# 3V3_LDO.net
KiCad netlist of a schematic drawn in Altium Designer
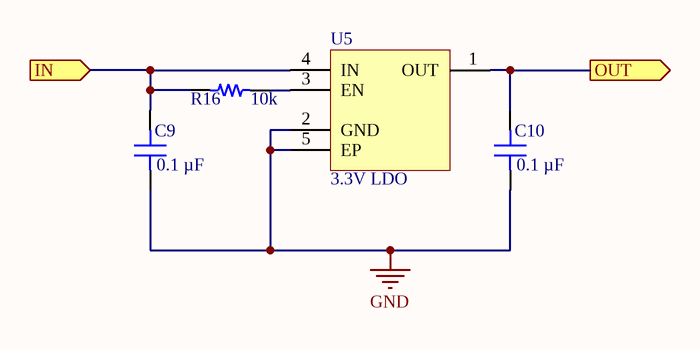
[diagram p0: 3V3_LDO.SchDoc]

(export (version "E")
  (design (tool "Eeschema 10.0.6"))
  (components
    (comp (ref "C9")
      (value "0.1 µF")
      (footprint "CAP 0402_1005")
      (description "CAP CER 0.1UF 16V X7R 0402")
      (fields (field (name "PART NUMBER") "C0402C104K4RACAUTO") (field (name "MANUFACTURER") "KEMET"))
      (libsource (lib "Celestial Altium Library - altium_library") (part "Capacitor"))
    )
    (comp (ref "C10")
      (value "0.1 µF")
      (footprint "CAP 0402_1005")
      (description "CAP CER 0.1UF 16V X7R 0402")
      (fields (field (name "PART NUMBER") "C0402C104K4RACAUTO") (field (name "MANUFACTURER") "KEMET"))
      (libsource (lib "Celestial Altium Library - altium_library") (part "Capacitor"))
    )
    (comp (ref "R16")
      (value "10k")
      (footprint "RES 0402_1005")
      (description "RES 5.62K OHM 0.1% 1/10W 0402")
      (fields
        (field (name "PART NUMBER") "RP73PF1E5K62BTD")
        (field (name "MANUFACTURER") "TE Connectivity Passive Product")
      )
      (libsource (lib "Celestial Altium Library - altium_library") (part "Resistor"))
    )
    (comp (ref "U5") (value "3.3V LDO") (footprint "XDFN-4") (libsource (lib "IC") (part "TLV74033PDQNR")))
  )
  (nets
    (net (code "1") (name "/IN") (class "Default")
      (node (ref "C9") (pin "2") (pinfunction "2_2") (pintype "passive"))
      (node (ref "R16") (pin "1") (pinfunction "1_1") (pintype "passive"))
      (node (ref "U5") (pin "4") (pinfunction "IN_4") (pintype "passive"))
    )
    (net (code "2") (name "/OUT") (class "Default")
      (node (ref "C10") (pin "2") (pinfunction "2_2") (pintype "passive"))
      (node (ref "U5") (pin "1") (pinfunction "OUT_1") (pintype "passive"))
    )
    (net (code "3") (name "GND") (class "Default")
      (node (ref "C10") (pin "1") (pinfunction "1_1") (pintype "passive"))
      (node (ref "C9") (pin "1") (pinfunction "1_1") (pintype "passive"))
      (node (ref "U5") (pin "2") (pinfunction "GND_2") (pintype "passive"))
      (node (ref "U5") (pin "5") (pinfunction "EP_5") (pintype "passive"))
    )
    (net (code "4") (name "Net-(U5-EN)") (class "Default")
      (node (ref "R16") (pin "2") (pinfunction "2_2") (pintype "passive"))
      (node (ref "U5") (pin "3") (pinfunction "EN_3") (pintype "passive"))
    )
  )
)
